# AUDIO.net
KiCad netlist of a schematic drawn in Altium Designer
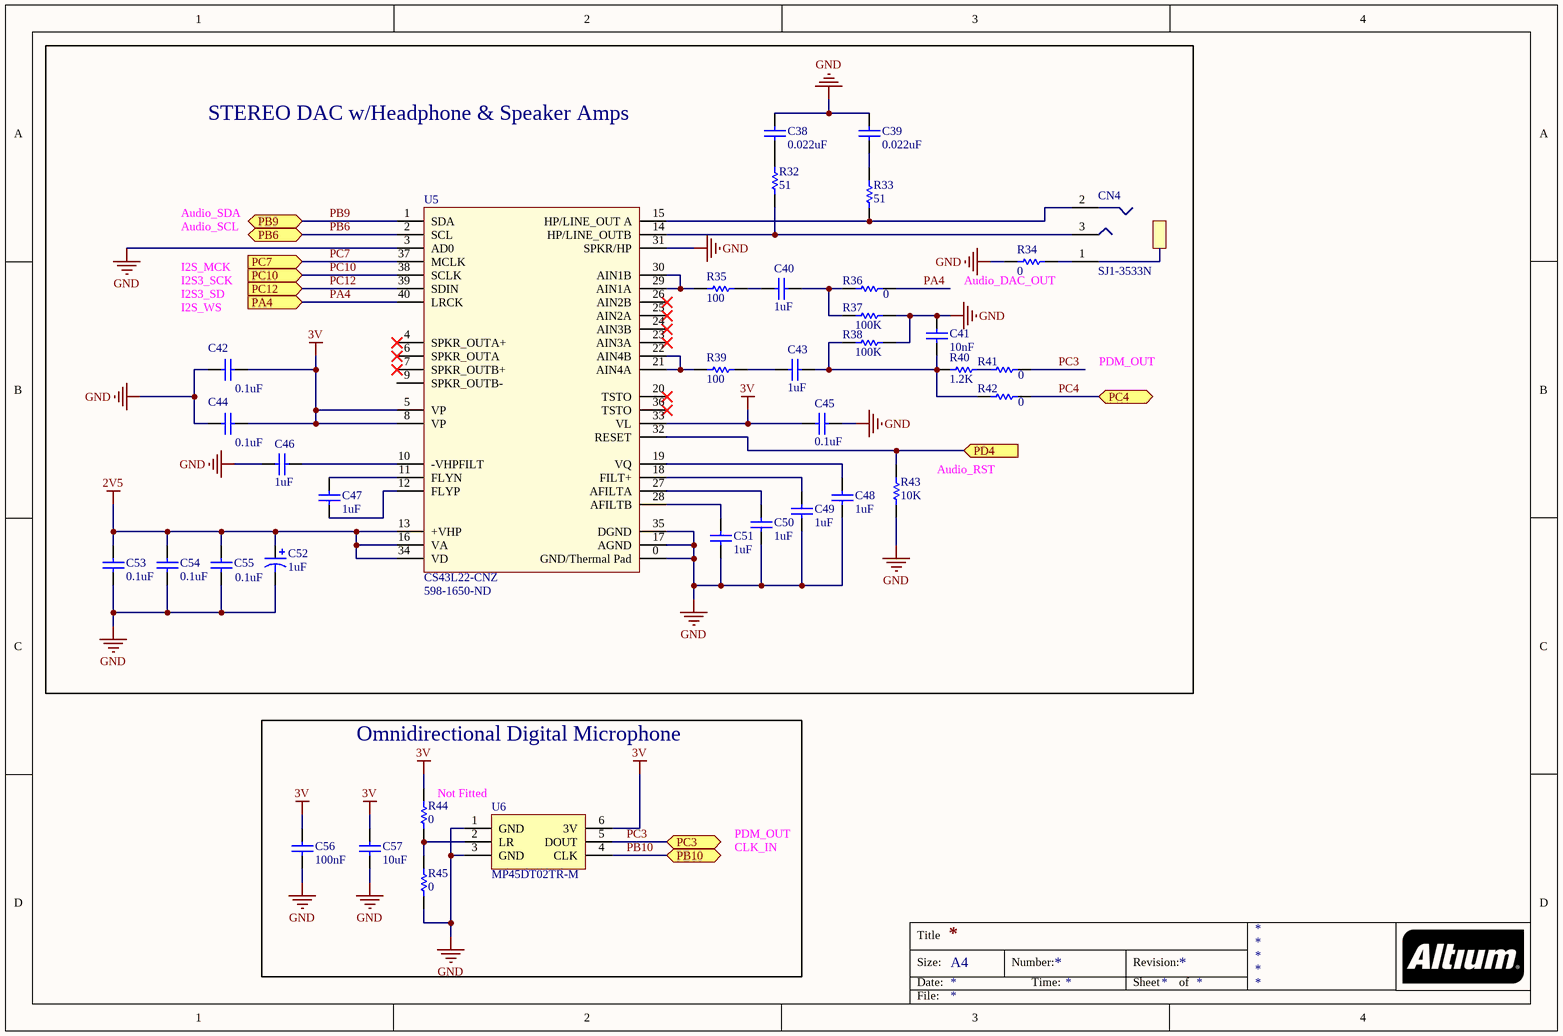
[diagram p0: AUDIO.SchDoc]

(export (version "E")
  (design (tool "Eeschema 10.0.6"))
  (components
    (comp (ref "C38")
      (value "0.022uF")
      (footprint "CAPC0402B")
      (description "Capacitor")
      (fields (field (name "Comment") "Cap") (field (name "PUBLISHER") "Altium Limited"))
      (libsource (lib "STM32F4DISCOVERY") (part "Cap_8"))
    )
    (comp (ref "C39")
      (value "0.022uF")
      (footprint "CAPC0402B")
      (description "Capacitor")
      (fields (field (name "Comment") "Cap") (field (name "PUBLISHER") "Altium Limited"))
      (libsource (lib "STM32F4DISCOVERY") (part "Cap_8"))
    )
    (comp (ref "C40")
      (value "1uF")
      (footprint "CAPC0603B")
      (description "Capacitor")
      (fields (field (name "Comment") "Cap") (field (name "PUBLISHER") "Altium Limited"))
      (libsource (lib "STM32F4DISCOVERY") (part "Cap_4"))
    )
    (comp (ref "C41")
      (value "10nF")
      (footprint "CAPC0402B")
      (description "Capacitor")
      (fields (field (name "Comment") "Cap") (field (name "PUBLISHER") "Altium Limited"))
      (libsource (lib "STM32F4DISCOVERY") (part "Cap_7"))
    )
    (comp (ref "C42")
      (value "0.1uF")
      (footprint "CAPC0402B")
      (description "Capacitor")
      (fields (field (name "Comment") "Cap") (field (name "PUBLISHER") "Altium Limited"))
      (libsource (lib "STM32F4DISCOVERY") (part "Cap_6"))
    )
    (comp (ref "C43")
      (value "1uF")
      (footprint "CAPC0603B")
      (description "Capacitor")
      (fields (field (name "Comment") "Cap") (field (name "PUBLISHER") "Altium Limited"))
      (libsource (lib "STM32F4DISCOVERY") (part "Cap_4"))
    )
    (comp (ref "C44")
      (value "0.1uF")
      (footprint "CAPC0402B")
      (description "Capacitor")
      (fields (field (name "Comment") "Cap") (field (name "PUBLISHER") "Altium Limited"))
      (libsource (lib "STM32F4DISCOVERY") (part "Cap_6"))
    )
    (comp (ref "C45")
      (value "0.1uF")
      (footprint "CAPC0402B")
      (description "Capacitor")
      (fields (field (name "Comment") "Cap") (field (name "PUBLISHER") "Altium Limited"))
      (libsource (lib "STM32F4DISCOVERY") (part "Cap_6"))
    )
    (comp (ref "C46")
      (value "1uF")
      (footprint "CAPC0603B")
      (description "Capacitor")
      (fields (field (name "Comment") "Cap") (field (name "PUBLISHER") "Altium Limited"))
      (libsource (lib "STM32F4DISCOVERY") (part "Cap_4"))
    )
    (comp (ref "C47")
      (value "1uF")
      (footprint "CAPC0603B")
      (description "Capacitor")
      (fields (field (name "Comment") "Cap") (field (name "PUBLISHER") "Altium Limited"))
      (libsource (lib "STM32F4DISCOVERY") (part "Cap_4"))
    )
    (comp (ref "C48")
      (value "1uF")
      (footprint "CAPC0603B")
      (description "Capacitor")
      (fields (field (name "Comment") "Cap") (field (name "PUBLISHER") "Altium Limited"))
      (libsource (lib "STM32F4DISCOVERY") (part "Cap_4"))
    )
    (comp (ref "C49")
      (value "1uF")
      (footprint "CAPC0603B")
      (description "Capacitor")
      (fields (field (name "Comment") "Cap") (field (name "PUBLISHER") "Altium Limited"))
      (libsource (lib "STM32F4DISCOVERY") (part "Cap_4"))
    )
    (comp (ref "C50")
      (value "1uF")
      (footprint "CAPC0603B")
      (description "Capacitor")
      (fields (field (name "Comment") "Cap") (field (name "PUBLISHER") "Altium Limited"))
      (libsource (lib "STM32F4DISCOVERY") (part "Cap_4"))
    )
    (comp (ref "C51")
      (value "1uF")
      (footprint "CAPC0603B")
      (description "Capacitor")
      (fields (field (name "Comment") "Cap") (field (name "PUBLISHER") "Altium Limited"))
      (libsource (lib "STM32F4DISCOVERY") (part "Cap_4"))
    )
    (comp (ref "C52")
      (value "1uF")
      (footprint "TANTALUM CASE A_LEVEL B")
      (description "Polarized Capacitor (Radial)")
      (fields (field (name "Comment") "Cap Pol1") (field (name "PUBLISHER") "Altium Limited"))
      (libsource (lib "STM32F4DISCOVERY") (part "Cap Pol1"))
    )
    (comp (ref "C53")
      (value "0.1uF")
      (footprint "CAPC0402B")
      (description "Capacitor")
      (fields (field (name "Comment") "Cap") (field (name "PUBLISHER") "Altium Limited"))
      (libsource (lib "STM32F4DISCOVERY") (part "Cap_6"))
    )
    (comp (ref "C54")
      (value "0.1uF")
      (footprint "CAPC0402B")
      (description "Capacitor")
      (fields (field (name "Comment") "Cap") (field (name "PUBLISHER") "Altium Limited"))
      (libsource (lib "STM32F4DISCOVERY") (part "Cap_6"))
    )
    (comp (ref "C55")
      (value "0.1uF")
      (footprint "CAPC0402B")
      (description "Capacitor")
      (fields (field (name "Comment") "Cap") (field (name "PUBLISHER") "Altium Limited"))
      (libsource (lib "STM32F4DISCOVERY") (part "Cap_6"))
    )
    (comp (ref "C56")
      (value "100nF")
      (footprint "CAPC0603B")
      (description "Capacitor")
      (fields (field (name "Comment") "Cap") (field (name "PUBLISHER") "Altium Limited"))
      (libsource (lib "STM32F4DISCOVERY") (part "Cap_3"))
    )
    (comp (ref "C57")
      (value "10uF")
      (footprint "CAPC0402B")
      (description "Capacitor")
      (fields (field (name "Comment") "Cap") (field (name "PUBLISHER") "Altium Limited"))
      (libsource (lib "STM32F4DISCOVERY") (part "Cap_5"))
    )
    (comp (ref "CN4")
      (value "SJ1-3533N")
      (footprint "SJ1-3533N")
      (description "3.50mm (0.141\", 1/8\", Mini Plug) - Headphone Phone Jack Stereo Connector Solder")
      (fields (field (name "MANUFACTURER") "CUI"))
      (libsource (lib "STM32F4DISCOVERY") (part "PHONE JACK 3.5mm"))
    )
    (comp (ref "R32")
      (value "51")
      (footprint "RESC0402B")
      (description "Resistor")
      (fields (field (name "Comment") "Res1") (field (name "PUBLISHER") "Altium Limited"))
      (libsource (lib "STM32F4DISCOVERY") (part "Res1_8"))
    )
    (comp (ref "R33")
      (value "51")
      (footprint "RESC0402B")
      (description "Resistor")
      (fields (field (name "Comment") "Res1") (field (name "PUBLISHER") "Altium Limited"))
      (libsource (lib "STM32F4DISCOVERY") (part "Res1_8"))
    )
    (comp (ref "R34")
      (value "0")
      (footprint "RESC0603B")
      (description "Resistor")
      (fields (field (name "Comment") "Res1") (field (name "PUBLISHER") "Altium Limited"))
      (libsource (lib "STM32F4DISCOVERY") (part "Res1"))
    )
    (comp (ref "R35")
      (value "100")
      (footprint "RESC0402B")
      (description "Resistor")
      (fields (field (name "Comment") "Res1") (field (name "PUBLISHER") "Altium Limited"))
      (libsource (lib "STM32F4DISCOVERY") (part "Res1_4"))
    )
    (comp (ref "R36")
      (value "0")
      (footprint "RESC0603B")
      (description "Resistor")
      (fields (field (name "Comment") "Res1") (field (name "PUBLISHER") "Altium Limited"))
      (libsource (lib "STM32F4DISCOVERY") (part "Res1"))
    )
    (comp (ref "R37")
      (value "100K")
      (footprint "RESC0402B")
      (description "Resistor")
      (fields (field (name "Comment") "Res1") (field (name "PUBLISHER") "Altium Limited"))
      (libsource (lib "STM32F4DISCOVERY") (part "Res1_5"))
    )
    (comp (ref "R38")
      (value "100K")
      (footprint "RESC0402B")
      (description "Resistor")
      (fields (field (name "Comment") "Res1") (field (name "PUBLISHER") "Altium Limited"))
      (libsource (lib "STM32F4DISCOVERY") (part "Res1_5"))
    )
    (comp (ref "R39")
      (value "100")
      (footprint "RESC0402B")
      (description "Resistor")
      (fields (field (name "Comment") "Res1") (field (name "PUBLISHER") "Altium Limited"))
      (libsource (lib "STM32F4DISCOVERY") (part "Res1_4"))
    )
    (comp (ref "R40")
      (value "1.2K")
      (footprint "RESC0402B")
      (description "Resistor")
      (fields (field (name "Comment") "Res1") (field (name "PUBLISHER") "Altium Limited"))
      (libsource (lib "STM32F4DISCOVERY") (part "Res1_7"))
    )
    (comp (ref "R41")
      (value "0")
      (footprint "RESC0603B")
      (description "Resistor")
      (fields (field (name "Comment") "Res1") (field (name "PUBLISHER") "Altium Limited"))
      (libsource (lib "STM32F4DISCOVERY") (part "Res1"))
    )
    (comp (ref "R42")
      (value "0")
      (footprint "RESC0603B")
      (description "Resistor")
      (fields (field (name "Comment") "Res1") (field (name "PUBLISHER") "Altium Limited"))
      (libsource (lib "STM32F4DISCOVERY") (part "Res1"))
    )
    (comp (ref "R43")
      (value "10K")
      (footprint "RESC0603B")
      (description "Resistor")
      (fields (field (name "Comment") "Res1") (field (name "PUBLISHER") "Altium Limited"))
      (libsource (lib "STM32F4DISCOVERY") (part "Res1_2"))
    )
    (comp (ref "R44")
      (value "0")
      (footprint "RESC0603B")
      (description "Resistor")
      (fields (field (name "Comment") "Res1") (field (name "PUBLISHER") "Altium Limited"))
      (libsource (lib "STM32F4DISCOVERY") (part "Res1"))
    )
    (comp (ref "R45")
      (value "0")
      (footprint "RESC0603B")
      (description "Resistor")
      (fields (field (name "Comment") "Res1") (field (name "PUBLISHER") "Altium Limited"))
      (libsource (lib "STM32F4DISCOVERY") (part "Res1"))
    )
    (comp (ref "U5")
      (value "CS43L22-CNZ")
      (footprint "40QFN")
      (fields
        (field (name "MANUFACTURER") "Cirrus Logic")
        (field (name "SUPPLIER PART NUMBER 1") "598-1650-ND")
      )
      (libsource (lib "STM32F4DISCOVERY") (part "CS43L22-CNZ"))
    )
    (comp (ref "U6")
      (value "MP45DT02TR-M")
      (footprint "MP45DT02TR")
      (libsource (lib "SMT32F407VGT6_LIB") (part "MP45DT02TR"))
    )
  )
  (nets
    (net (code "1") (name "/PA4") (class "Default")
      (node (ref "R36") (pin "2") (pinfunction "2_2") (pintype "passive"))
      (node (ref "U5") (pin "40") (pinfunction "LRCK_40") (pintype "passive"))
    )
    (net (code "2") (name "/PB6") (class "Default")
      (node (ref "U5") (pin "2") (pinfunction "SCL_2") (pintype "passive"))
    )
    (net (code "3") (name "/PB9") (class "Default")
      (node (ref "U5") (pin "1") (pinfunction "SDA_1") (pintype "passive"))
    )
    (net (code "4") (name "/PB10") (class "Default")
      (node (ref "U6") (pin "4") (pinfunction "CLK_4") (pintype "passive"))
    )
    (net (code "5") (name "/PC3") (class "Default")
      (node (ref "R41") (pin "2") (pinfunction "2_2") (pintype "passive"))
      (node (ref "U6") (pin "5") (pinfunction "DOUT_5") (pintype "passive"))
    )
    (net (code "6") (name "/PC4") (class "Default")
      (node (ref "R42") (pin "2") (pinfunction "2_2") (pintype "passive"))
    )
    (net (code "7") (name "/PC7") (class "Default")
      (node (ref "U5") (pin "37") (pinfunction "MCLK_37") (pintype "passive"))
    )
    (net (code "8") (name "/PC10") (class "Default")
      (node (ref "U5") (pin "38") (pinfunction "SCLK_38") (pintype "passive"))
    )
    (net (code "9") (name "/PC12") (class "Default")
      (node (ref "U5") (pin "39") (pinfunction "SDIN_39") (pintype "passive"))
    )
    (net (code "10") (name "/PD4") (class "Default")
      (node (ref "R43") (pin "2") (pinfunction "2_2") (pintype "passive"))
      (node (ref "U5") (pin "32") (pinfunction "RESET_32") (pintype "passive"))
    )
    (net (code "11") (name "2V5") (class "Default")
      (node (ref "C52") (pin "1") (pinfunction "1_1") (pintype "passive"))
      (node (ref "C53") (pin "2") (pinfunction "2_2") (pintype "passive"))
      (node (ref "C54") (pin "2") (pinfunction "2_2") (pintype "passive"))
      (node (ref "C55") (pin "2") (pinfunction "2_2") (pintype "passive"))
      (node (ref "U5") (pin "13") (pinfunction "+VHP_13") (pintype "passive"))
      (node (ref "U5") (pin "16") (pinfunction "VA_16") (pintype "passive"))
      (node (ref "U5") (pin "34") (pinfunction "VD_34") (pintype "passive"))
    )
    (net (code "12") (name "3V") (class "Default")
      (node (ref "C42") (pin "2") (pinfunction "2_2") (pintype "passive"))
      (node (ref "C44") (pin "2") (pinfunction "2_2") (pintype "passive"))
      (node (ref "C45") (pin "2") (pinfunction "2_2") (pintype "passive"))
      (node (ref "C56") (pin "2") (pinfunction "2_2") (pintype "passive"))
      (node (ref "C57") (pin "2") (pinfunction "2_2") (pintype "passive"))
      (node (ref "R44") (pin "2") (pinfunction "2_2") (pintype "passive"))
      (node (ref "U5") (pin "33") (pinfunction "VL_33") (pintype "passive"))
      (node (ref "U5") (pin "5") (pinfunction "VP_5") (pintype "passive"))
      (node (ref "U5") (pin "8") (pinfunction "VP_8") (pintype "passive"))
      (node (ref "U6") (pin "6") (pinfunction "3V_6") (pintype "passive"))
    )
    (net (code "13") (name "GND") (class "Default")
      (node (ref "C38") (pin "2") (pinfunction "2_2") (pintype "passive"))
      (node (ref "C39") (pin "2") (pinfunction "2_2") (pintype "passive"))
      (node (ref "C41") (pin "2") (pinfunction "2_2") (pintype "passive"))
      (node (ref "C42") (pin "1") (pinfunction "1_1") (pintype "passive"))
      (node (ref "C44") (pin "1") (pinfunction "1_1") (pintype "passive"))
      (node (ref "C45") (pin "1") (pinfunction "1_1") (pintype "passive"))
      (node (ref "C46") (pin "1") (pinfunction "1_1") (pintype "passive"))
      (node (ref "C48") (pin "2") (pinfunction "2_2") (pintype "passive"))
      (node (ref "C49") (pin "2") (pinfunction "2_2") (pintype "passive"))
      (node (ref "C50") (pin "2") (pinfunction "2_2") (pintype "passive"))
      (node (ref "C51") (pin "1") (pinfunction "1_1") (pintype "passive"))
      (node (ref "C52") (pin "2") (pinfunction "2_2") (pintype "passive"))
      (node (ref "C53") (pin "1") (pinfunction "1_1") (pintype "passive"))
      (node (ref "C54") (pin "1") (pinfunction "1_1") (pintype "passive"))
      (node (ref "C55") (pin "1") (pinfunction "1_1") (pintype "passive"))
      (node (ref "C56") (pin "1") (pinfunction "1_1") (pintype "passive"))
      (node (ref "C57") (pin "1") (pinfunction "1_1") (pintype "passive"))
      (node (ref "R34") (pin "1") (pinfunction "1_1") (pintype "passive"))
      (node (ref "R37") (pin "2") (pinfunction "2_2") (pintype "passive"))
      (node (ref "R38") (pin "2") (pinfunction "2_2") (pintype "passive"))
      (node (ref "R43") (pin "1") (pinfunction "1_1") (pintype "passive"))
      (node (ref "R45") (pin "1") (pinfunction "1_1") (pintype "passive"))
      (node (ref "U5") (pin "0") (pinfunction "GND/Thermal_Pad_0") (pintype "passive"))
      (node (ref "U5") (pin "17") (pinfunction "AGND_17") (pintype "passive"))
      (node (ref "U5") (pin "3") (pinfunction "AD0_3") (pintype "passive"))
      (node (ref "U5") (pin "31") (pinfunction "SPKR/HP_31") (pintype "passive"))
      (node (ref "U5") (pin "35") (pinfunction "DGND_35") (pintype "passive"))
      (node (ref "U6") (pin "1") (pinfunction "GND_1") (pintype "passive"))
      (node (ref "U6") (pin "3") (pinfunction "GND_3") (pintype "passive"))
    )
    (net (code "14") (name "Net-(C38-Pad1)") (class "Default")
      (node (ref "C38") (pin "1") (pinfunction "1_1") (pintype "passive"))
      (node (ref "R32") (pin "2") (pinfunction "2_2") (pintype "passive"))
    )
    (net (code "15") (name "Net-(C39-Pad1)") (class "Default")
      (node (ref "C39") (pin "1") (pinfunction "1_1") (pintype "passive"))
      (node (ref "R33") (pin "2") (pinfunction "2_2") (pintype "passive"))
    )
    (net (code "16") (name "Net-(C40-Pad1)") (class "Default")
      (node (ref "C40") (pin "1") (pinfunction "1_1") (pintype "passive"))
      (node (ref "R35") (pin "1") (pinfunction "1_1") (pintype "passive"))
    )
    (net (code "17") (name "Net-(C40-Pad2)") (class "Default")
      (node (ref "C40") (pin "2") (pinfunction "2_2") (pintype "passive"))
      (node (ref "R36") (pin "1") (pinfunction "1_1") (pintype "passive"))
      (node (ref "R37") (pin "1") (pinfunction "1_1") (pintype "passive"))
    )
    (net (code "18") (name "Net-(C41-Pad1)") (class "Default")
      (node (ref "C41") (pin "1") (pinfunction "1_1") (pintype "passive"))
      (node (ref "C43") (pin "2") (pinfunction "2_2") (pintype "passive"))
      (node (ref "R38") (pin "1") (pinfunction "1_1") (pintype "passive"))
      (node (ref "R40") (pin "1") (pinfunction "1_1") (pintype "passive"))
      (node (ref "R42") (pin "1") (pinfunction "1_1") (pintype "passive"))
    )
    (net (code "19") (name "Net-(C43-Pad1)") (class "Default")
      (node (ref "C43") (pin "1") (pinfunction "1_1") (pintype "passive"))
      (node (ref "R39") (pin "1") (pinfunction "1_1") (pintype "passive"))
    )
    (net (code "20") (name "Net-(CN4-Pad1)") (class "Default")
      (node (ref "CN4") (pin "1") (pinfunction "1_1") (pintype "passive"))
      (node (ref "R34") (pin "2") (pinfunction "2_2") (pintype "passive"))
    )
    (net (code "21") (name "Net-(R40-Pad2)") (class "Default")
      (node (ref "R40") (pin "2") (pinfunction "2_2") (pintype "passive"))
      (node (ref "R41") (pin "1") (pinfunction "1_1") (pintype "passive"))
    )
    (net (code "22") (name "Net-(U5--VHPFILT)") (class "Default")
      (node (ref "C46") (pin "2") (pinfunction "2_2") (pintype "passive"))
      (node (ref "U5") (pin "10") (pinfunction "-VHPFILT_10") (pintype "passive"))
    )
    (net (code "23") (name "Net-(U5-AFILTA)") (class "Default")
      (node (ref "C50") (pin "1") (pinfunction "1_1") (pintype "passive"))
      (node (ref "U5") (pin "27") (pinfunction "AFILTA_27") (pintype "passive"))
    )
    (net (code "24") (name "Net-(U5-AFILTB)") (class "Default")
      (node (ref "C51") (pin "2") (pinfunction "2_2") (pintype "passive"))
      (node (ref "U5") (pin "28") (pinfunction "AFILTB_28") (pintype "passive"))
    )
    (net (code "25") (name "Net-(U5-AIN1A)") (class "Default")
      (node (ref "R35") (pin "2") (pinfunction "2_2") (pintype "passive"))
      (node (ref "U5") (pin "29") (pinfunction "AIN1A_29") (pintype "passive"))
      (node (ref "U5") (pin "30") (pinfunction "AIN1B_30") (pintype "passive"))
    )
    (net (code "26") (name "Net-(U5-AIN4A)") (class "Default")
      (node (ref "R39") (pin "2") (pinfunction "2_2") (pintype "passive"))
      (node (ref "U5") (pin "21") (pinfunction "AIN4A_21") (pintype "passive"))
      (node (ref "U5") (pin "22") (pinfunction "AIN4B_22") (pintype "passive"))
    )
    (net (code "27") (name "Net-(U5-FILT+)") (class "Default")
      (node (ref "C49") (pin "1") (pinfunction "1_1") (pintype "passive"))
      (node (ref "U5") (pin "18") (pinfunction "FILT+_18") (pintype "passive"))
    )
    (net (code "28") (name "Net-(U5-FLYN)") (class "Default")
      (node (ref "C47") (pin "2") (pinfunction "2_2") (pintype "passive"))
      (node (ref "U5") (pin "11") (pinfunction "FLYN_11") (pintype "passive"))
    )
    (net (code "29") (name "Net-(U5-FLYP)") (class "Default")
      (node (ref "C47") (pin "1") (pinfunction "1_1") (pintype "passive"))
      (node (ref "U5") (pin "12") (pinfunction "FLYP_12") (pintype "passive"))
    )
    (net (code "30") (name "Net-(U5-HP{slash}LINE_OUTB)") (class "Default")
      (node (ref "CN4") (pin "3") (pinfunction "3_3") (pintype "passive"))
      (node (ref "R32") (pin "1") (pinfunction "1_1") (pintype "passive"))
      (node (ref "U5") (pin "14") (pinfunction "HP/LINE_OUTB_14") (pintype "passive"))
    )
    (net (code "31") (name "Net-(U5-HP{slash}LINE_OUT_A)") (class "Default")
      (node (ref "CN4") (pin "2") (pinfunction "2_2") (pintype "passive"))
      (node (ref "R33") (pin "1") (pinfunction "1_1") (pintype "passive"))
      (node (ref "U5") (pin "15") (pinfunction "HP/LINE_OUT_A_15") (pintype "passive"))
    )
    (net (code "32") (name "Net-(U5-VQ)") (class "Default")
      (node (ref "C48") (pin "1") (pinfunction "1_1") (pintype "passive"))
      (node (ref "U5") (pin "19") (pinfunction "VQ_19") (pintype "passive"))
    )
    (net (code "33") (name "Net-(U6-LR)") (class "Default")
      (node (ref "R44") (pin "1") (pinfunction "1_1") (pintype "passive"))
      (node (ref "R45") (pin "2") (pinfunction "2_2") (pintype "passive"))
      (node (ref "U6") (pin "2") (pinfunction "LR_2") (pintype "passive"))
    )
    (net (code "34") (name "unconnected-(U5-AIN2A-Pad25)") (class "Default")
      (node (ref "U5") (pin "25") (pinfunction "AIN2A_25") (pintype "passive+no_connect"))
    )
    (net (code "35") (name "unconnected-(U5-AIN2B-Pad26)") (class "Default")
      (node (ref "U5") (pin "26") (pinfunction "AIN2B_26") (pintype "passive+no_connect"))
    )
    (net (code "36") (name "unconnected-(U5-AIN3A-Pad23)") (class "Default")
      (node (ref "U5") (pin "23") (pinfunction "AIN3A_23") (pintype "passive+no_connect"))
    )
    (net (code "37") (name "unconnected-(U5-AIN3B-Pad24)") (class "Default")
      (node (ref "U5") (pin "24") (pinfunction "AIN3B_24") (pintype "passive+no_connect"))
    )
    (net (code "38") (name "unconnected-(U5-SPKR_OUTA+-Pad4)") (class "Default")
      (node (ref "U5") (pin "4") (pinfunction "SPKR_OUTA+_4") (pintype "passive+no_connect"))
    )
    (net (code "39") (name "unconnected-(U5-SPKR_OUTA-Pad6)") (class "Default")
      (node (ref "U5") (pin "6") (pinfunction "SPKR_OUTA_6") (pintype "passive+no_connect"))
    )
    (net (code "40") (name "unconnected-(U5-SPKR_OUTB+-Pad7)") (class "Default")
      (node (ref "U5") (pin "7") (pinfunction "SPKR_OUTB+_7") (pintype "passive+no_connect"))
    )
    (net (code "41") (name "unconnected-(U5-SPKR_OUTB--Pad9)") (class "Default")
      (node (ref "U5") (pin "9") (pinfunction "SPKR_OUTB-_9") (pintype "passive"))
    )
    (net (code "42") (name "unconnected-(U5-TSTO-Pad20)") (class "Default")
      (node (ref "U5") (pin "20") (pinfunction "TSTO_20") (pintype "passive+no_connect"))
    )
    (net (code "43") (name "unconnected-(U5-TSTO-Pad36)") (class "Default")
      (node (ref "U5") (pin "36") (pinfunction "TSTO_36") (pintype "passive+no_connect"))
    )
  )
)
